# sensors.net
KiCad netlist of a schematic drawn in EAGLE
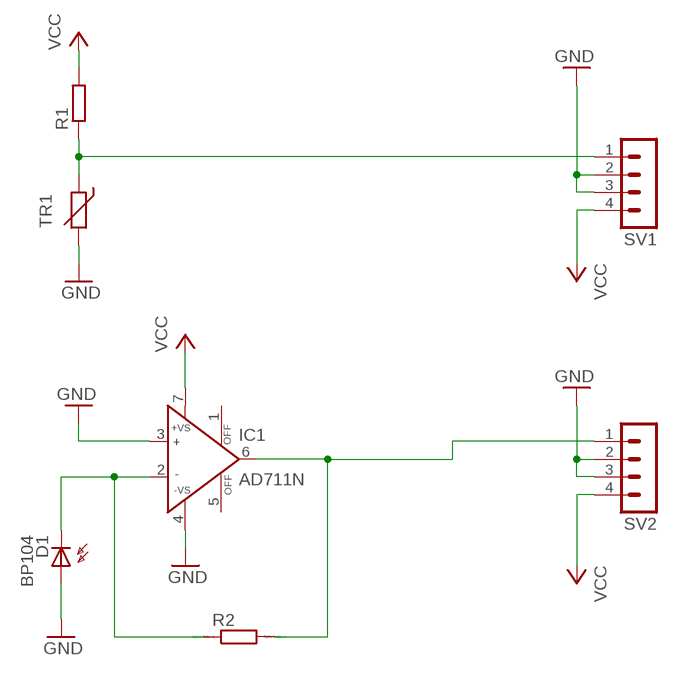
[diagram p0: schematic, sheet 1]

(export (version "E")
  (design (tool "Eeschema 10.0.6"))
  (components
    (comp (ref "D1")
      (value "BP104")
      (footprint "eagle-import:BP104")
      (fields (field (name "MF") "VISHAY/TELEFUNKEN"))
      (libsource (lib "eagle-import") (part "BP104"))
    )
    (comp (ref "IC1")
      (value "AD711N")
      (footprint "eagle-import:DIL08")
      (fields (field (name "MPN") "AD711BQ"))
      (libsource (lib "eagle-import") (part "AD711N"))
    )
    (comp (ref "R1")
      (value "R-EU_0204/7")
      (footprint "eagle-import:0204_7")
      (libsource (lib "eagle-import") (part "R-EU_0204/7"))
    )
    (comp (ref "R2")
      (value "R0204/7")
      (footprint "eagle-import:0204_7")
      (libsource (lib "eagle-import") (part "R0204/7"))
    )
    (comp (ref "SV1")
      (value "MA04-1")
      (footprint "eagle-import:MA04-1")
      (libsource (lib "eagle-import") (part "MA04-1"))
    )
    (comp (ref "SV2")
      (value "MA04-1")
      (footprint "eagle-import:MA04-1")
      (libsource (lib "eagle-import") (part "MA04-1"))
    )
    (comp (ref "TR1")
      (value "THERMISTOR_")
      (footprint "eagle-import:TO92")
      (libsource (lib "eagle-import") (part "THERMISTOR_"))
    )
  )
  (nets
    (net (code "1") (name "GND") (class "Default")
      (node (ref "D1") (pin "A") (pinfunction "A_A") (pintype "passive"))
      (node (ref "IC1") (pin "3") (pinfunction "IN+_3") (pintype "input"))
      (node (ref "IC1") (pin "4") (pinfunction "-VS_4") (pintype "input"))
      (node (ref "SV1") (pin "2") (pinfunction "2_2") (pintype "passive"))
      (node (ref "SV1") (pin "3") (pinfunction "3_3") (pintype "passive"))
      (node (ref "SV2") (pin "2") (pinfunction "2_2") (pintype "passive"))
      (node (ref "SV2") (pin "3") (pinfunction "3_3") (pintype "passive"))
      (node (ref "TR1") (pin "2") (pinfunction "2_2") (pintype "passive"))
    )
    (net (code "2") (name "Net-(D1-C)") (class "Default")
      (node (ref "D1") (pin "K") (pinfunction "C_K") (pintype "passive"))
      (node (ref "IC1") (pin "2") (pinfunction "IN-_2") (pintype "input"))
      (node (ref "R2") (pin "1") (pinfunction "1_1") (pintype "passive"))
    )
    (net (code "3") (name "Net-(IC1-OUT)") (class "Default")
      (node (ref "IC1") (pin "6") (pinfunction "OUT_6") (pintype "output"))
      (node (ref "R2") (pin "2") (pinfunction "2_2") (pintype "passive"))
      (node (ref "SV2") (pin "1") (pinfunction "1_1") (pintype "passive"))
    )
    (net (code "4") (name "Net-(R1-Pad1)") (class "Default")
      (node (ref "R1") (pin "1") (pinfunction "1_1") (pintype "passive"))
      (node (ref "SV1") (pin "1") (pinfunction "1_1") (pintype "passive"))
      (node (ref "TR1") (pin "1") (pinfunction "1_1") (pintype "passive"))
    )
    (net (code "5") (name "VCC") (class "Default")
      (node (ref "IC1") (pin "7") (pinfunction "+VS_7") (pintype "input"))
      (node (ref "R1") (pin "2") (pinfunction "2_2") (pintype "passive"))
      (node (ref "SV1") (pin "4") (pinfunction "4_4") (pintype "passive"))
      (node (ref "SV2") (pin "4") (pinfunction "4_4") (pintype "passive"))
    )
    (net (code "6") (name "unconnected-(IC1-OFF-Pad1)") (class "Default")
      (node (ref "IC1") (pin "1") (pinfunction "OFF_1") (pintype "passive"))
    )
    (net (code "7") (name "unconnected-(IC1-OFF-Pad5)") (class "Default")
      (node (ref "IC1") (pin "5") (pinfunction "OFF_5") (pintype "passive"))
    )
  )
)
